# 5_power.net
KiCad netlist of a schematic drawn in Altium Designer
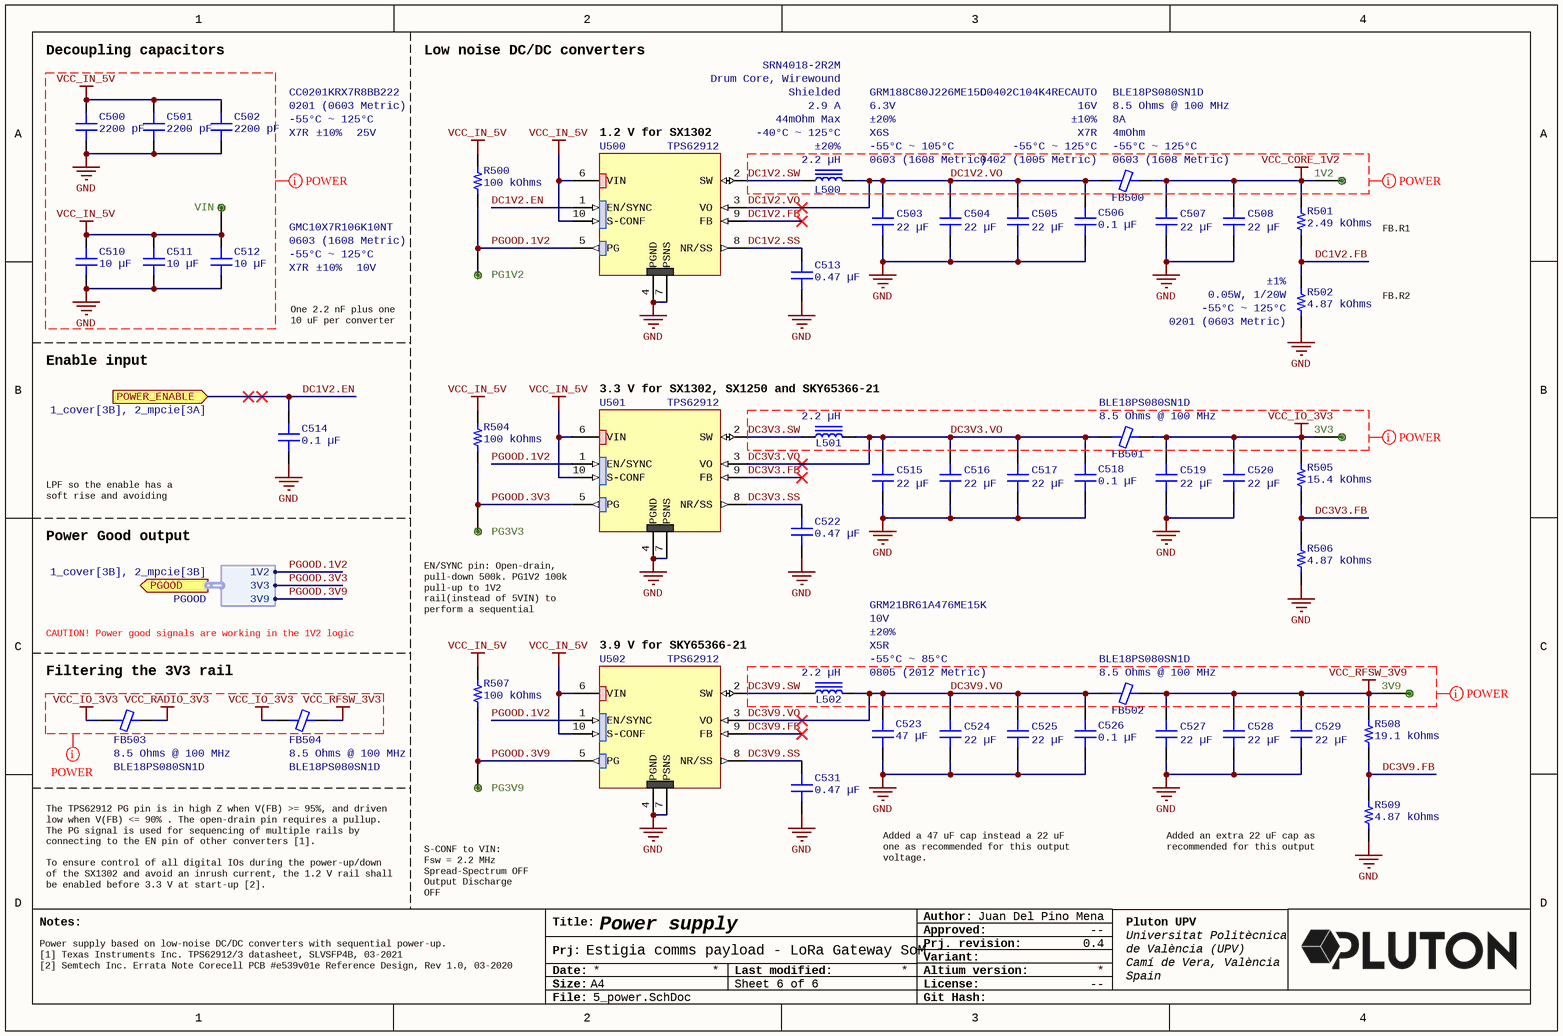
[diagram p0: 5_power.SchDoc]

(export (version "E")
  (design (tool "Eeschema 10.0.6"))
  (components
    (comp (ref "1V2")
      (value "~")
      (footprint "testpoints:testpoint_via")
      (description "Test point, thru-hole")
      (libsource (lib "testpoints") (part "TestPoint-VIA"))
    )
    (comp (ref "3V3")
      (value "~")
      (footprint "testpoints:testpoint_via")
      (description "Test point, thru-hole")
      (libsource (lib "testpoints") (part "TestPoint-VIA"))
    )
    (comp (ref "3V9")
      (value "~")
      (footprint "testpoints:testpoint_via")
      (description "Test point, thru-hole")
      (libsource (lib "testpoints") (part "TestPoint-VIA"))
    )
    (comp (ref "C500")
      (value "2200 pF")
      (footprint "CAP 0201_0603")
      (description "CAP CER 2200PF 25V X7R 0201")
      (fields (field (name "PART NUMBER") "CC0201KRX7R8BB222") (field (name "MANUFACTURER") "Yageo"))
      (libsource (lib "Celestial Altium Library - altium_library") (part "Capacitor"))
    )
    (comp (ref "C501")
      (value "2200 pF")
      (footprint "CAP 0201_0603")
      (description "CAP CER 2200PF 25V X7R 0201")
      (fields (field (name "PART NUMBER") "CC0201KRX7R8BB222") (field (name "MANUFACTURER") "Yageo"))
      (libsource (lib "Celestial Altium Library - altium_library") (part "Capacitor"))
    )
    (comp (ref "C502")
      (value "2200 pF")
      (footprint "CAP 0201_0603")
      (description "CAP CER 2200PF 25V X7R 0201")
      (fields
        (field (name "PART NUMBER") "CC0201KRX7R8BB222")
        (field (name "DEVICE PACKAGE") "0201 (0603 Metric)")
        (field (name "MANUFACTURER") "Yageo")
        (field (name "OPERATING TEMPERATURE") "-55°C ~ 125°C")
        (field (name "TEMPERATURE COEFFICIENT") "X7R")
        (field (name "TOLERANCE") "±10%")
        (field (name "VOLTAGE - RATED") "25V")
      )
      (libsource (lib "Celestial Altium Library - altium_library") (part "Capacitor"))
    )
    (comp (ref "C503")
      (value "22 µF")
      (footprint "CAP 0603_1608")
      (description "CAP CER 22UF 6.3V X6S 0603")
      (fields
        (field (name "PART NUMBER") "GRM188C80J226ME15D")
        (field (name "DEVICE PACKAGE") "0603 (1608 Metric)")
        (field (name "MANUFACTURER") "Murata Electronics")
        (field (name "OPERATING TEMPERATURE") "-55°C ~ 105°C")
        (field (name "TEMPERATURE COEFFICIENT") "X6S")
        (field (name "TOLERANCE") "±20%")
        (field (name "VOLTAGE - RATED") "6.3V")
      )
      (libsource (lib "Celestial Altium Library - altium_library") (part "Capacitor"))
    )
    (comp (ref "C504")
      (value "22 µF")
      (footprint "CAP 0603_1608")
      (description "CAP CER 22UF 6.3V X6S 0603")
      (fields
        (field (name "PART NUMBER") "GRM188C80J226ME15D")
        (field (name "MANUFACTURER") "Murata Electronics")
      )
      (libsource (lib "Celestial Altium Library - altium_library") (part "Capacitor"))
    )
    (comp (ref "C505")
      (value "22 µF")
      (footprint "CAP 0603_1608")
      (description "CAP CER 22UF 6.3V X6S 0603")
      (fields
        (field (name "PART NUMBER") "GRM188C80J226ME15D")
        (field (name "MANUFACTURER") "Murata Electronics")
      )
      (libsource (lib "Celestial Altium Library - altium_library") (part "Capacitor"))
    )
    (comp (ref "C506")
      (value "0.1 µF")
      (footprint "CAP 0402_1005")
      (description "CAP CER 0402 0.1UF 16V X7R 10%")
      (fields
        (field (name "PART NUMBER") "C0402C104K4RECAUTO")
        (field (name "MANUFACTURER") "KEMET")
        (field (name "OPERATING TEMPERATURE") "-55°C ~ 125°C")
        (field (name "PACKAGE / CASE") "0402 (1005 Metric)")
        (field (name "TEMPERATURE COEFFICIENT") "X7R")
        (field (name "TOLERANCE") "±10%")
        (field (name "VOLTAGE - RATED") "16V")
      )
      (libsource (lib "Celestial Altium Library - altium_library") (part "Capacitor"))
    )
    (comp (ref "C507")
      (value "22 µF")
      (footprint "CAP 0603_1608")
      (description "CAP CER 22UF 6.3V X6S 0603")
      (fields
        (field (name "PART NUMBER") "GRM188C80J226ME15D")
        (field (name "MANUFACTURER") "Murata Electronics")
      )
      (libsource (lib "Celestial Altium Library - altium_library") (part "Capacitor"))
    )
    (comp (ref "C508")
      (value "22 µF")
      (footprint "CAP 0603_1608")
      (description "CAP CER 22UF 6.3V X6S 0603")
      (fields
        (field (name "PART NUMBER") "GRM188C80J226ME15D")
        (field (name "MANUFACTURER") "Murata Electronics")
      )
      (libsource (lib "Celestial Altium Library - altium_library") (part "Capacitor"))
    )
    (comp (ref "C510")
      (value "10 µF")
      (footprint "CAP 0603_1608")
      (description "CAP0603 X7R 10UF 10% 10V")
      (fields
        (field (name "PART NUMBER") "GMC10X7R106K10NT")
        (field (name "MANUFACTURER") "Cal-Chip Electronics, Inc.")
      )
      (libsource (lib "Celestial Altium Library - altium_library") (part "Capacitor"))
    )
    (comp (ref "C511")
      (value "10 µF")
      (footprint "CAP 0603_1608")
      (description "CAP0603 X7R 10UF 10% 10V")
      (fields
        (field (name "PART NUMBER") "GMC10X7R106K10NT")
        (field (name "MANUFACTURER") "Cal-Chip Electronics, Inc.")
      )
      (libsource (lib "Celestial Altium Library - altium_library") (part "Capacitor"))
    )
    (comp (ref "C512")
      (value "10 µF")
      (footprint "CAP 0603_1608")
      (description "CAP0603 X7R 10UF 10% 10V")
      (fields
        (field (name "PART NUMBER") "GMC10X7R106K10NT")
        (field (name "DEVICE PACKAGE") "0603 (1608 Metric)")
        (field (name "MANUFACTURER") "Cal-Chip Electronics, Inc.")
        (field (name "OPERATING TEMPERATURE") "-55°C ~ 125°C")
        (field (name "TEMPERATURE COEFFICIENT") "X7R")
        (field (name "TOLERANCE") "±10%")
        (field (name "VOLTAGE - RATED") "10V")
      )
      (libsource (lib "Celestial Altium Library - altium_library") (part "Capacitor"))
    )
    (comp (ref "C513")
      (value "0.47 µF")
      (footprint "CAP 0402_1005")
      (description "CAP CER 0.47UF 16V X7S 0402")
      (fields
        (field (name "PART NUMBER") "CGA2B1X7S1C474K050BC")
        (field (name "MANUFACTURER") "TDK Corporation")
      )
      (libsource (lib "Celestial Altium Library - altium_library") (part "Capacitor"))
    )
    (comp (ref "C514")
      (value "0.1 µF")
      (footprint "CAP 0402_1005")
      (description "CAP CER 0402 0.1UF 16V X7R 10%")
      (fields (field (name "PART NUMBER") "C0402C104K4RECAUTO") (field (name "MANUFACTURER") "KEMET"))
      (libsource (lib "Celestial Altium Library - altium_library") (part "Capacitor"))
    )
    (comp (ref "C515")
      (value "22 µF")
      (footprint "CAP 0603_1608")
      (description "CAP CER 22UF 6.3V X6S 0603")
      (fields
        (field (name "PART NUMBER") "GRM188C80J226ME15D")
        (field (name "MANUFACTURER") "Murata Electronics")
      )
      (libsource (lib "Celestial Altium Library - altium_library") (part "Capacitor"))
    )
    (comp (ref "C516")
      (value "22 µF")
      (footprint "CAP 0603_1608")
      (description "CAP CER 22UF 6.3V X6S 0603")
      (fields
        (field (name "PART NUMBER") "GRM188C80J226ME15D")
        (field (name "MANUFACTURER") "Murata Electronics")
      )
      (libsource (lib "Celestial Altium Library - altium_library") (part "Capacitor"))
    )
    (comp (ref "C517")
      (value "22 µF")
      (footprint "CAP 0603_1608")
      (description "CAP CER 22UF 6.3V X6S 0603")
      (fields
        (field (name "PART NUMBER") "GRM188C80J226ME15D")
        (field (name "MANUFACTURER") "Murata Electronics")
      )
      (libsource (lib "Celestial Altium Library - altium_library") (part "Capacitor"))
    )
    (comp (ref "C518")
      (value "0.1 µF")
      (footprint "CAP 0402_1005")
      (description "CAP CER 0402 0.1UF 16V X7R 10%")
      (fields (field (name "PART NUMBER") "C0402C104K4RECAUTO") (field (name "MANUFACTURER") "KEMET"))
      (libsource (lib "Celestial Altium Library - altium_library") (part "Capacitor"))
    )
    (comp (ref "C519")
      (value "22 µF")
      (footprint "CAP 0603_1608")
      (description "CAP CER 22UF 6.3V X6S 0603")
      (fields
        (field (name "PART NUMBER") "GRM188C80J226ME15D")
        (field (name "MANUFACTURER") "Murata Electronics")
      )
      (libsource (lib "Celestial Altium Library - altium_library") (part "Capacitor"))
    )
    (comp (ref "C520")
      (value "22 µF")
      (footprint "CAP 0603_1608")
      (description "CAP CER 22UF 6.3V X6S 0603")
      (fields
        (field (name "PART NUMBER") "GRM188C80J226ME15D")
        (field (name "MANUFACTURER") "Murata Electronics")
      )
      (libsource (lib "Celestial Altium Library - altium_library") (part "Capacitor"))
    )
    (comp (ref "C522")
      (value "0.47 µF")
      (footprint "CAP 0402_1005")
      (description "CAP CER 0.47UF 16V X7S 0402")
      (fields
        (field (name "PART NUMBER") "CGA2B1X7S1C474K050BC")
        (field (name "MANUFACTURER") "TDK Corporation")
      )
      (libsource (lib "Celestial Altium Library - altium_library") (part "Capacitor"))
    )
    (comp (ref "C523")
      (value "47 µF")
      (footprint "CAP 0805_2012")
      (description "CAP CER 47UF 10V X5R 0805")
      (fields
        (field (name "PART NUMBER") "GRM21BR61A476ME15K")
        (field (name "DEVICE PACKAGE") "0805 (2012 Metric)")
        (field (name "MANUFACTURER") "Murata Electronics")
        (field (name "OPERATING TEMPERATURE") "-55°C ~ 85°C")
        (field (name "TEMPERATURE COEFFICIENT") "X5R")
        (field (name "TOLERANCE") "±20%")
        (field (name "VOLTAGE - RATED") "10V")
      )
      (libsource (lib "Celestial Altium Library - altium_library") (part "Capacitor"))
    )
    (comp (ref "C524")
      (value "22 µF")
      (footprint "CAP 0603_1608")
      (description "CAP CER 22UF 6.3V X6S 0603")
      (fields
        (field (name "PART NUMBER") "GRM188C80J226ME15D")
        (field (name "MANUFACTURER") "Murata Electronics")
      )
      (libsource (lib "Celestial Altium Library - altium_library") (part "Capacitor"))
    )
    (comp (ref "C525")
      (value "22 µF")
      (footprint "CAP 0603_1608")
      (description "CAP CER 22UF 6.3V X6S 0603")
      (fields
        (field (name "PART NUMBER") "GRM188C80J226ME15D")
        (field (name "MANUFACTURER") "Murata Electronics")
      )
      (libsource (lib "Celestial Altium Library - altium_library") (part "Capacitor"))
    )
    (comp (ref "C526")
      (value "0.1 µF")
      (footprint "CAP 0402_1005")
      (description "CAP CER 0402 0.1UF 16V X7R 10%")
      (fields (field (name "PART NUMBER") "C0402C104K4RECAUTO") (field (name "MANUFACTURER") "KEMET"))
      (libsource (lib "Celestial Altium Library - altium_library") (part "Capacitor"))
    )
    (comp (ref "C527")
      (value "22 µF")
      (footprint "CAP 0603_1608")
      (description "CAP CER 22UF 6.3V X6S 0603")
      (fields
        (field (name "PART NUMBER") "GRM188C80J226ME15D")
        (field (name "MANUFACTURER") "Murata Electronics")
      )
      (libsource (lib "Celestial Altium Library - altium_library") (part "Capacitor"))
    )
    (comp (ref "C528")
      (value "22 µF")
      (footprint "CAP 0603_1608")
      (description "CAP CER 22UF 6.3V X6S 0603")
      (fields
        (field (name "PART NUMBER") "GRM188C80J226ME15D")
        (field (name "MANUFACTURER") "Murata Electronics")
      )
      (libsource (lib "Celestial Altium Library - altium_library") (part "Capacitor"))
    )
    (comp (ref "C529")
      (value "22 µF")
      (footprint "CAP 0603_1608")
      (description "CAP CER 22UF 6.3V X6S 0603")
      (fields
        (field (name "PART NUMBER") "GRM188C80J226ME15D")
        (field (name "MANUFACTURER") "Murata Electronics")
      )
      (libsource (lib "Celestial Altium Library - altium_library") (part "Capacitor"))
    )
    (comp (ref "C531")
      (value "0.47 µF")
      (footprint "CAP 0402_1005")
      (description "CAP CER 0.47UF 16V X7S 0402")
      (fields
        (field (name "PART NUMBER") "CGA2B1X7S1C474K050BC")
        (field (name "MANUFACTURER") "TDK Corporation")
      )
      (libsource (lib "Celestial Altium Library - altium_library") (part "Capacitor"))
    )
    (comp (ref "FB500")
      (value "8.5 Ohms @ 100 MHz")
      (footprint "FER 0603_1608")
      (description "FERRITE BEAD 8.5 OHM 0603 1LN")
      (fields
        (field (name "PART NUMBER") "BLE18PS080SN1D")
        (field (name "CURRENT RATING (MAX)") "8A")
        (field (name "DC RESISTANCE (DCR) (MAX)") "4mOhm")
        (field (name "DEVICE PACKAGE") "0603 (1608 Metric)")
        (field (name "IMPEDANCE @ FREQUENCY") "8.5 Ohms @ 100 MHz")
        (field (name "MANUFACTURER") "Murata Electronics")
        (field (name "OPERATING TEMPERATURE") "-55°C ~ 125°C")
      )
      (libsource (lib "Celestial Altium Library - altium_library") (part "Ferrite Chip"))
    )
    (comp (ref "FB501")
      (value "8.5 Ohms @ 100 MHz")
      (footprint "FER 0603_1608")
      (description "FERRITE BEAD 8.5 OHM 0603 1LN")
      (fields
        (field (name "PART NUMBER") "BLE18PS080SN1D")
        (field (name "IMPEDANCE @ FREQUENCY") "8.5 Ohms @ 100 MHz")
        (field (name "MANUFACTURER") "Murata Electronics")
      )
      (libsource (lib "Celestial Altium Library - altium_library") (part "Ferrite Chip"))
    )
    (comp (ref "FB502")
      (value "8.5 Ohms @ 100 MHz")
      (footprint "FER 0603_1608")
      (description "FERRITE BEAD 8.5 OHM 0603 1LN")
      (fields
        (field (name "PART NUMBER") "BLE18PS080SN1D")
        (field (name "IMPEDANCE @ FREQUENCY") "8.5 Ohms @ 100 MHz")
        (field (name "MANUFACTURER") "Murata Electronics")
      )
      (libsource (lib "Celestial Altium Library - altium_library") (part "Ferrite Chip"))
    )
    (comp (ref "FB503")
      (value "8.5 Ohms @ 100 MHz")
      (footprint "FER 0603_1608")
      (description "FERRITE BEAD 8.5 OHM 0603 1LN")
      (fields
        (field (name "PART NUMBER") "BLE18PS080SN1D")
        (field (name "IMPEDANCE @ FREQUENCY") "8.5 Ohms @ 100 MHz")
        (field (name "MANUFACTURER") "Murata Electronics")
      )
      (libsource (lib "Celestial Altium Library - altium_library") (part "Ferrite Chip"))
    )
    (comp (ref "FB504")
      (value "8.5 Ohms @ 100 MHz")
      (footprint "FER 0603_1608")
      (description "FERRITE BEAD 8.5 OHM 0603 1LN")
      (fields
        (field (name "PART NUMBER") "BLE18PS080SN1D")
        (field (name "IMPEDANCE @ FREQUENCY") "8.5 Ohms @ 100 MHz")
        (field (name "MANUFACTURER") "Murata Electronics")
      )
      (libsource (lib "Celestial Altium Library - altium_library") (part "Ferrite Chip"))
    )
    (comp (ref "L500")
      (value "2.2 µH")
      (footprint "BOURNS SRN4018")
      (description "FIXED IND 2.2UH 2.9A 44 MOHM SMD")
      (fields
        (field (name "PART NUMBER") "SRN4018-2R2M")
        (field (name "CURRENT RATING (AMPS)") "2.9 A")
        (field (name "DC RESISTANCE (DCR)") "44mOhm Max")
        (field (name "MANUFACTURER") "Bourns Inc.")
        (field (name "OPERATING TEMPERATURE") "-40°C ~ 125°C")
        (field (name "SHIELDING") "Shielded")
        (field (name "TOLERANCE") "±20%")
        (field (name "TYPE") "Drum Core, Wirewound")
      )
      (libsource (lib "Celestial Altium Library - altium_library") (part "Inductor"))
    )
    (comp (ref "L501")
      (value "2.2 µH")
      (footprint "BOURNS SRN4018")
      (description "FIXED IND 2.2UH 2.9A 44 MOHM SMD")
      (fields (field (name "PART NUMBER") "SRN4018-2R2M") (field (name "MANUFACTURER") "Bourns Inc."))
      (libsource (lib "Celestial Altium Library - altium_library") (part "Inductor"))
    )
    (comp (ref "L502")
      (value "2.2 µH")
      (footprint "BOURNS SRN4018")
      (description "FIXED IND 2.2UH 2.9A 44 MOHM SMD")
      (fields (field (name "PART NUMBER") "SRN4018-2R2M") (field (name "MANUFACTURER") "Bourns Inc."))
      (libsource (lib "Celestial Altium Library - altium_library") (part "Inductor"))
    )
    (comp (ref "PG1V2")
      (value "~")
      (footprint "testpoints:testpoint_via")
      (description "Test point, thru-hole")
      (libsource (lib "testpoints") (part "TestPoint-VIA"))
    )
    (comp (ref "PG3V3")
      (value "~")
      (footprint "testpoints:testpoint_via")
      (description "Test point, thru-hole")
      (libsource (lib "testpoints") (part "TestPoint-VIA"))
    )
    (comp (ref "PG3V9")
      (value "~")
      (footprint "testpoints:testpoint_via")
      (description "Test point, thru-hole")
      (libsource (lib "testpoints") (part "TestPoint-VIA"))
    )
    (comp (ref "R500")
      (value "100 kOhms")
      (footprint "RES 0201_0603")
      (description "RES 100K OHM 1% 1/20W 0201")
      (fields (field (name "PART NUMBER") "RC0201FR-13100KL") (field (name "MANUFACTURER") "Yageo"))
      (libsource (lib "Celestial Altium Library - altium_library") (part "Resistor"))
    )
    (comp (ref "R501")
      (value "2.49 kOhms")
      (footprint "RES 0201_0603")
      (description "RES SMD 2.49K OHM 1% 1/20W 0201")
      (fields (field (name "PART NUMBER") "AC0201FR-072K49L") (field (name "MANUFACTURER") "Yageo"))
      (libsource (lib "Celestial Altium Library - altium_library") (part "Resistor"))
    )
    (comp (ref "R502")
      (value "4.87 kOhms")
      (footprint "RES 0201_0603")
      (description "RES 4.87K OHM 1% 1/20W 0201")
      (fields
        (field (name "PART NUMBER") "RC0201FR-074K87L")
        (field (name "DEVICE PACKAGE") "0201 (0603 Metric)")
        (field (name "MANUFACTURER") "Yageo")
        (field (name "OPERATING TEMPERATURE") "-55°C ~ 125°C")
        (field (name "POWER (WATTS)") "0.05W, 1/20W")
        (field (name "TOLERANCE") "±1%")
      )
      (libsource (lib "Celestial Altium Library - altium_library") (part "Resistor"))
    )
    (comp (ref "R504")
      (value "100 kOhms")
      (footprint "RES 0201_0603")
      (description "RES 100K OHM 1% 1/20W 0201")
      (fields (field (name "PART NUMBER") "RC0201FR-13100KL") (field (name "MANUFACTURER") "Yageo"))
      (libsource (lib "Celestial Altium Library - altium_library") (part "Resistor"))
    )
    (comp (ref "R505")
      (value "15.4 kOhms")
      (footprint "RES 0201_0603")
      (description "RES 15.4K OHM 1% 1/20W 0201")
      (fields (field (name "PART NUMBER") "RC0201FR-0715K4L") (field (name "MANUFACTURER") "Yageo"))
      (libsource (lib "Celestial Altium Library - altium_library") (part "Resistor"))
    )
    (comp (ref "R506")
      (value "4.87 kOhms")
      (footprint "RES 0201_0603")
      (description "RES 4.87K OHM 1% 1/20W 0201")
      (fields (field (name "PART NUMBER") "RC0201FR-074K87L") (field (name "MANUFACTURER") "Yageo"))
      (libsource (lib "Celestial Altium Library - altium_library") (part "Resistor"))
    )
    (comp (ref "R507")
      (value "100 kOhms")
      (footprint "RES 0201_0603")
      (description "RES 100K OHM 1% 1/20W 0201")
      (fields (field (name "PART NUMBER") "RC0201FR-13100KL") (field (name "MANUFACTURER") "Yageo"))
      (libsource (lib "Celestial Altium Library - altium_library") (part "Resistor"))
    )
    (comp (ref "R508")
      (value "19.1 kOhms")
      (footprint "RES 0201_0603")
      (description "RES 19.1K OHM 1% 1/20W 0201")
      (fields (field (name "PART NUMBER") "RC0201FR-0719K1L") (field (name "MANUFACTURER") "Yageo"))
      (libsource (lib "Celestial Altium Library - altium_library") (part "Resistor"))
    )
    (comp (ref "R509")
      (value "4.87 kOhms")
      (footprint "RES 0201_0603")
      (description "RES 4.87K OHM 1% 1/20W 0201")
      (fields (field (name "PART NUMBER") "RC0201FR-074K87L") (field (name "MANUFACTURER") "Yageo"))
      (libsource (lib "Celestial Altium Library - altium_library") (part "Resistor"))
    )
    (comp (ref "U500")
      (value "TPS62912")
      (footprint "ics:VQFN-HR-TPS6291X")
      (libsource (lib "power") (part "TPS62912"))
    )
    (comp (ref "U501")
      (value "TPS62912")
      (footprint "ics:VQFN-HR-TPS6291X")
      (libsource (lib "power") (part "TPS62912"))
    )
    (comp (ref "U502")
      (value "TPS62912")
      (footprint "ics:VQFN-HR-TPS6291X")
      (libsource (lib "power") (part "TPS62912"))
    )
    (comp (ref "VIN")
      (value "~")
      (footprint "testpoints:testpoint_via")
      (description "Test point, thru-hole")
      (libsource (lib "testpoints") (part "TestPoint-VIA"))
    )
  )
  (nets
    (net (code "2") (name "/DC1V2.EN") (class "Default")
      (node (ref "C514") (pin "2") (pinfunction "2_2") (pintype "passive"))
      (node (ref "U500") (pin "1") (pinfunction "EN/SYNC_1") (pintype "input"))
    )
    (net (code "3") (name "/DC1V2.FB") (class "Default")
      (node (ref "R501") (pin "1") (pinfunction "1_1") (pintype "passive"))
      (node (ref "R502") (pin "2") (pinfunction "2_2") (pintype "passive"))
      (node (ref "U500") (pin "9") (pinfunction "FB_9") (pintype "input"))
    )
    (net (code "4") (name "/DC1V2.SS") (class "Default")
      (node (ref "C513") (pin "2") (pinfunction "2_2") (pintype "passive"))
      (node (ref "U500") (pin "8") (pinfunction "NR/SS_8") (pintype "output"))
    )
    (net (code "5") (name "/DC1V2.SW") (class "Default")
      (node (ref "L500") (pin "1") (pinfunction "1_1") (pintype "passive"))
      (node (ref "U500") (pin "2") (pinfunction "SW_2") (pintype "bidirectional"))
    )
    (net (code "6") (name "/DC1V2.VO") (class "Default")
      (node (ref "C503") (pin "2") (pinfunction "2_2") (pintype "passive"))
      (node (ref "C504") (pin "2") (pinfunction "2_2") (pintype "passive"))
      (node (ref "C505") (pin "2") (pinfunction "2_2") (pintype "passive"))
      (node (ref "C506") (pin "2") (pinfunction "2_2") (pintype "passive"))
      (node (ref "FB500") (pin "1") (pinfunction "1_1") (pintype "passive"))
      (node (ref "L500") (pin "2") (pinfunction "2_2") (pintype "passive"))
      (node (ref "U500") (pin "3") (pinfunction "VO_3") (pintype "input"))
    )
    (net (code "7") (name "/DC3V3.FB") (class "Default")
      (node (ref "R505") (pin "1") (pinfunction "1_1") (pintype "passive"))
      (node (ref "R506") (pin "2") (pinfunction "2_2") (pintype "passive"))
      (node (ref "U501") (pin "9") (pinfunction "FB_9") (pintype "input"))
    )
    (net (code "8") (name "/DC3V3.SS") (class "Default")
      (node (ref "C522") (pin "2") (pinfunction "2_2") (pintype "passive"))
      (node (ref "U501") (pin "8") (pinfunction "NR/SS_8") (pintype "output"))
    )
    (net (code "9") (name "/DC3V3.SW") (class "Default")
      (node (ref "L501") (pin "1") (pinfunction "1_1") (pintype "passive"))
      (node (ref "U501") (pin "2") (pinfunction "SW_2") (pintype "bidirectional"))
    )
    (net (code "10") (name "/DC3V3.VO") (class "Default")
      (node (ref "C515") (pin "2") (pinfunction "2_2") (pintype "passive"))
      (node (ref "C516") (pin "2") (pinfunction "2_2") (pintype "passive"))
      (node (ref "C517") (pin "2") (pinfunction "2_2") (pintype "passive"))
      (node (ref "C518") (pin "2") (pinfunction "2_2") (pintype "passive"))
      (node (ref "FB501") (pin "1") (pinfunction "1_1") (pintype "passive"))
      (node (ref "L501") (pin "2") (pinfunction "2_2") (pintype "passive"))
      (node (ref "U501") (pin "3") (pinfunction "VO_3") (pintype "input"))
    )
    (net (code "11") (name "/DC3V9.FB") (class "Default")
      (node (ref "R508") (pin "1") (pinfunction "1_1") (pintype "passive"))
      (node (ref "R509") (pin "2") (pinfunction "2_2") (pintype "passive"))
      (node (ref "U502") (pin "9") (pinfunction "FB_9") (pintype "input"))
    )
    (net (code "12") (name "/DC3V9.SS") (class "Default")
      (node (ref "C531") (pin "2") (pinfunction "2_2") (pintype "passive"))
      (node (ref "U502") (pin "8") (pinfunction "NR/SS_8") (pintype "output"))
    )
    (net (code "13") (name "/DC3V9.SW") (class "Default")
      (node (ref "L502") (pin "1") (pinfunction "1_1") (pintype "passive"))
      (node (ref "U502") (pin "2") (pinfunction "SW_2") (pintype "bidirectional"))
    )
    (net (code "14") (name "/DC3V9.VO") (class "Default")
      (node (ref "C523") (pin "2") (pinfunction "2_2") (pintype "passive"))
      (node (ref "C524") (pin "2") (pinfunction "2_2") (pintype "passive"))
      (node (ref "C525") (pin "2") (pinfunction "2_2") (pintype "passive"))
      (node (ref "C526") (pin "2") (pinfunction "2_2") (pintype "passive"))
      (node (ref "FB502") (pin "1") (pinfunction "1_1") (pintype "passive"))
      (node (ref "L502") (pin "2") (pinfunction "2_2") (pintype "passive"))
      (node (ref "U502") (pin "3") (pinfunction "VO_3") (pintype "input"))
    )
    (net (code "15") (name "/PGOOD.1V2") (class "Default")
      (node (ref "PG1V2") (pin "0") (pinfunction "0_0") (pintype "passive"))
      (node (ref "R500") (pin "1") (pinfunction "1_1") (pintype "passive"))
      (node (ref "U500") (pin "5") (pinfunction "PG_5") (pintype "output"))
      (node (ref "U501") (pin "1") (pinfunction "EN/SYNC_1") (pintype "input"))
      (node (ref "U502") (pin "1") (pinfunction "EN/SYNC_1") (pintype "input"))
    )
    (net (code "16") (name "/PGOOD.3V3") (class "Default")
      (node (ref "PG3V3") (pin "0") (pinfunction "0_0") (pintype "passive"))
      (node (ref "R504") (pin "1") (pinfunction "1_1") (pintype "passive"))
      (node (ref "U501") (pin "5") (pinfunction "PG_5") (pintype "output"))
    )
    (net (code "17") (name "/PGOOD.3V9") (class "Default")
      (node (ref "PG3V9") (pin "0") (pinfunction "0_0") (pintype "passive"))
      (node (ref "R507") (pin "1") (pinfunction "1_1") (pintype "passive"))
      (node (ref "U502") (pin "5") (pinfunction "PG_5") (pintype "output"))
    )
    (net (code "19") (name "GND") (class "Default")
      (node (ref "C500") (pin "1") (pinfunction "1_1") (pintype "passive"))
      (node (ref "C501") (pin "1") (pinfunction "1_1") (pintype "passive"))
      (node (ref "C502") (pin "1") (pinfunction "1_1") (pintype "passive"))
      (node (ref "C503") (pin "1") (pinfunction "1_1") (pintype "passive"))
      (node (ref "C504") (pin "1") (pinfunction "1_1") (pintype "passive"))
      (node (ref "C505") (pin "1") (pinfunction "1_1") (pintype "passive"))
      (node (ref "C506") (pin "1") (pinfunction "1_1") (pintype "passive"))
      (node (ref "C507") (pin "1") (pinfunction "1_1") (pintype "passive"))
      (node (ref "C508") (pin "1") (pinfunction "1_1") (pintype "passive"))
      (node (ref "C510") (pin "1") (pinfunction "1_1") (pintype "passive"))
      (node (ref "C511") (pin "1") (pinfunction "1_1") (pintype "passive"))
      (node (ref "C512") (pin "1") (pinfunction "1_1") (pintype "passive"))
      (node (ref "C513") (pin "1") (pinfunction "1_1") (pintype "passive"))
      (node (ref "C514") (pin "1") (pinfunction "1_1") (pintype "passive"))
      (node (ref "C515") (pin "1") (pinfunction "1_1") (pintype "passive"))
      (node (ref "C516") (pin "1") (pinfunction "1_1") (pintype "passive"))
      (node (ref "C517") (pin "1") (pinfunction "1_1") (pintype "passive"))
      (node (ref "C518") (pin "1") (pinfunction "1_1") (pintype "passive"))
      (node (ref "C519") (pin "1") (pinfunction "1_1") (pintype "passive"))
      (node (ref "C520") (pin "1") (pinfunction "1_1") (pintype "passive"))
      (node (ref "C522") (pin "1") (pinfunction "1_1") (pintype "passive"))
      (node (ref "C523") (pin "1") (pinfunction "1_1") (pintype "passive"))
      (node (ref "C524") (pin "1") (pinfunction "1_1") (pintype "passive"))
      (node (ref "C525") (pin "1") (pinfunction "1_1") (pintype "passive"))
      (node (ref "C526") (pin "1") (pinfunction "1_1") (pintype "passive"))
      (node (ref "C527") (pin "1") (pinfunction "1_1") (pintype "passive"))
      (node (ref "C528") (pin "1") (pinfunction "1_1") (pintype "passive"))
      (node (ref "C529") (pin "1") (pinfunction "1_1") (pintype "passive"))
      (node (ref "C531") (pin "1") (pinfunction "1_1") (pintype "passive"))
      (node (ref "R502") (pin "1") (pinfunction "1_1") (pintype "passive"))
      (node (ref "R506") (pin "1") (pinfunction "1_1") (pintype "passive"))
      (node (ref "R509") (pin "1") (pinfunction "1_1") (pintype "passive"))
      (node (ref "U500") (pin "4") (pinfunction "PGND_4") (pintype "passive"))
      (node (ref "U500") (pin "7") (pinfunction "PSNS_7") (pintype "power_in"))
      (node (ref "U501") (pin "4") (pinfunction "PGND_4") (pintype "passive"))
      (node (ref "U501") (pin "7") (pinfunction "PSNS_7") (pintype "power_in"))
      (node (ref "U502") (pin "4") (pinfunction "PGND_4") (pintype "passive"))
      (node (ref "U502") (pin "7") (pinfunction "PSNS_7") (pintype "power_in"))
    )
    (net (code "20") (name "VCC_CORE_1V2") (class "Default")
      (node (ref "1V2") (pin "0") (pinfunction "0_0") (pintype "passive"))
      (node (ref "C507") (pin "2") (pinfunction "2_2") (pintype "passive"))
      (node (ref "C508") (pin "2") (pinfunction "2_2") (pintype "passive"))
      (node (ref "FB500") (pin "2") (pinfunction "2_2") (pintype "passive"))
      (node (ref "R501") (pin "2") (pinfunction "2_2") (pintype "passive"))
    )
    (net (code "21") (name "VCC_IN_5V") (class "Default")
      (node (ref "C500") (pin "2") (pinfunction "2_2") (pintype "passive"))
      (node (ref "C501") (pin "2") (pinfunction "2_2") (pintype "passive"))
      (node (ref "C502") (pin "2") (pinfunction "2_2") (pintype "passive"))
      (node (ref "C510") (pin "2") (pinfunction "2_2") (pintype "passive"))
      (node (ref "C511") (pin "2") (pinfunction "2_2") (pintype "passive"))
      (node (ref "C512") (pin "2") (pinfunction "2_2") (pintype "passive"))
      (node (ref "R500") (pin "2") (pinfunction "2_2") (pintype "passive"))
      (node (ref "R504") (pin "2") (pinfunction "2_2") (pintype "passive"))
      (node (ref "R507") (pin "2") (pinfunction "2_2") (pintype "passive"))
      (node (ref "U500") (pin "10") (pinfunction "S-CONF_10") (pintype "input"))
      (node (ref "U500") (pin "6") (pinfunction "VIN_6") (pintype "power_in"))
      (node (ref "U501") (pin "10") (pinfunction "S-CONF_10") (pintype "input"))
      (node (ref "U501") (pin "6") (pinfunction "VIN_6") (pintype "power_in"))
      (node (ref "U502") (pin "10") (pinfunction "S-CONF_10") (pintype "input"))
      (node (ref "U502") (pin "6") (pinfunction "VIN_6") (pintype "power_in"))
      (node (ref "VIN") (pin "0") (pinfunction "0_0") (pintype "passive"))
    )
    (net (code "22") (name "VCC_IO_3V3") (class "Default")
      (node (ref "3V3") (pin "0") (pinfunction "0_0") (pintype "passive"))
      (node (ref "C519") (pin "2") (pinfunction "2_2") (pintype "passive"))
      (node (ref "C520") (pin "2") (pinfunction "2_2") (pintype "passive"))
      (node (ref "FB501") (pin "2") (pinfunction "2_2") (pintype "passive"))
      (node (ref "FB503") (pin "1") (pinfunction "1_1") (pintype "passive"))
      (node (ref "FB504") (pin "1") (pinfunction "1_1") (pintype "passive"))
      (node (ref "R505") (pin "2") (pinfunction "2_2") (pintype "passive"))
    )
    (net (code "23") (name "VCC_RADIO_3V3") (class "Default")
      (node (ref "FB503") (pin "2") (pinfunction "2_2") (pintype "passive"))
    )
    (net (code "24") (name "VCC_RFSW_3V3") (class "Default")
      (node (ref "FB504") (pin "2") (pinfunction "2_2") (pintype "passive"))
    )
    (net (code "25") (name "VCC_RFSW_3V9") (class "Default")
      (node (ref "3V9") (pin "0") (pinfunction "0_0") (pintype "passive"))
      (node (ref "C527") (pin "2") (pinfunction "2_2") (pintype "passive"))
      (node (ref "C528") (pin "2") (pinfunction "2_2") (pintype "passive"))
      (node (ref "C529") (pin "2") (pinfunction "2_2") (pintype "passive"))
      (node (ref "FB502") (pin "2") (pinfunction "2_2") (pintype "passive"))
      (node (ref "R508") (pin "2") (pinfunction "2_2") (pintype "passive"))
    )
  )
)
